# Page_C_ExCONNECTOR.net
KiCad netlist of a schematic drawn in Altium Designer
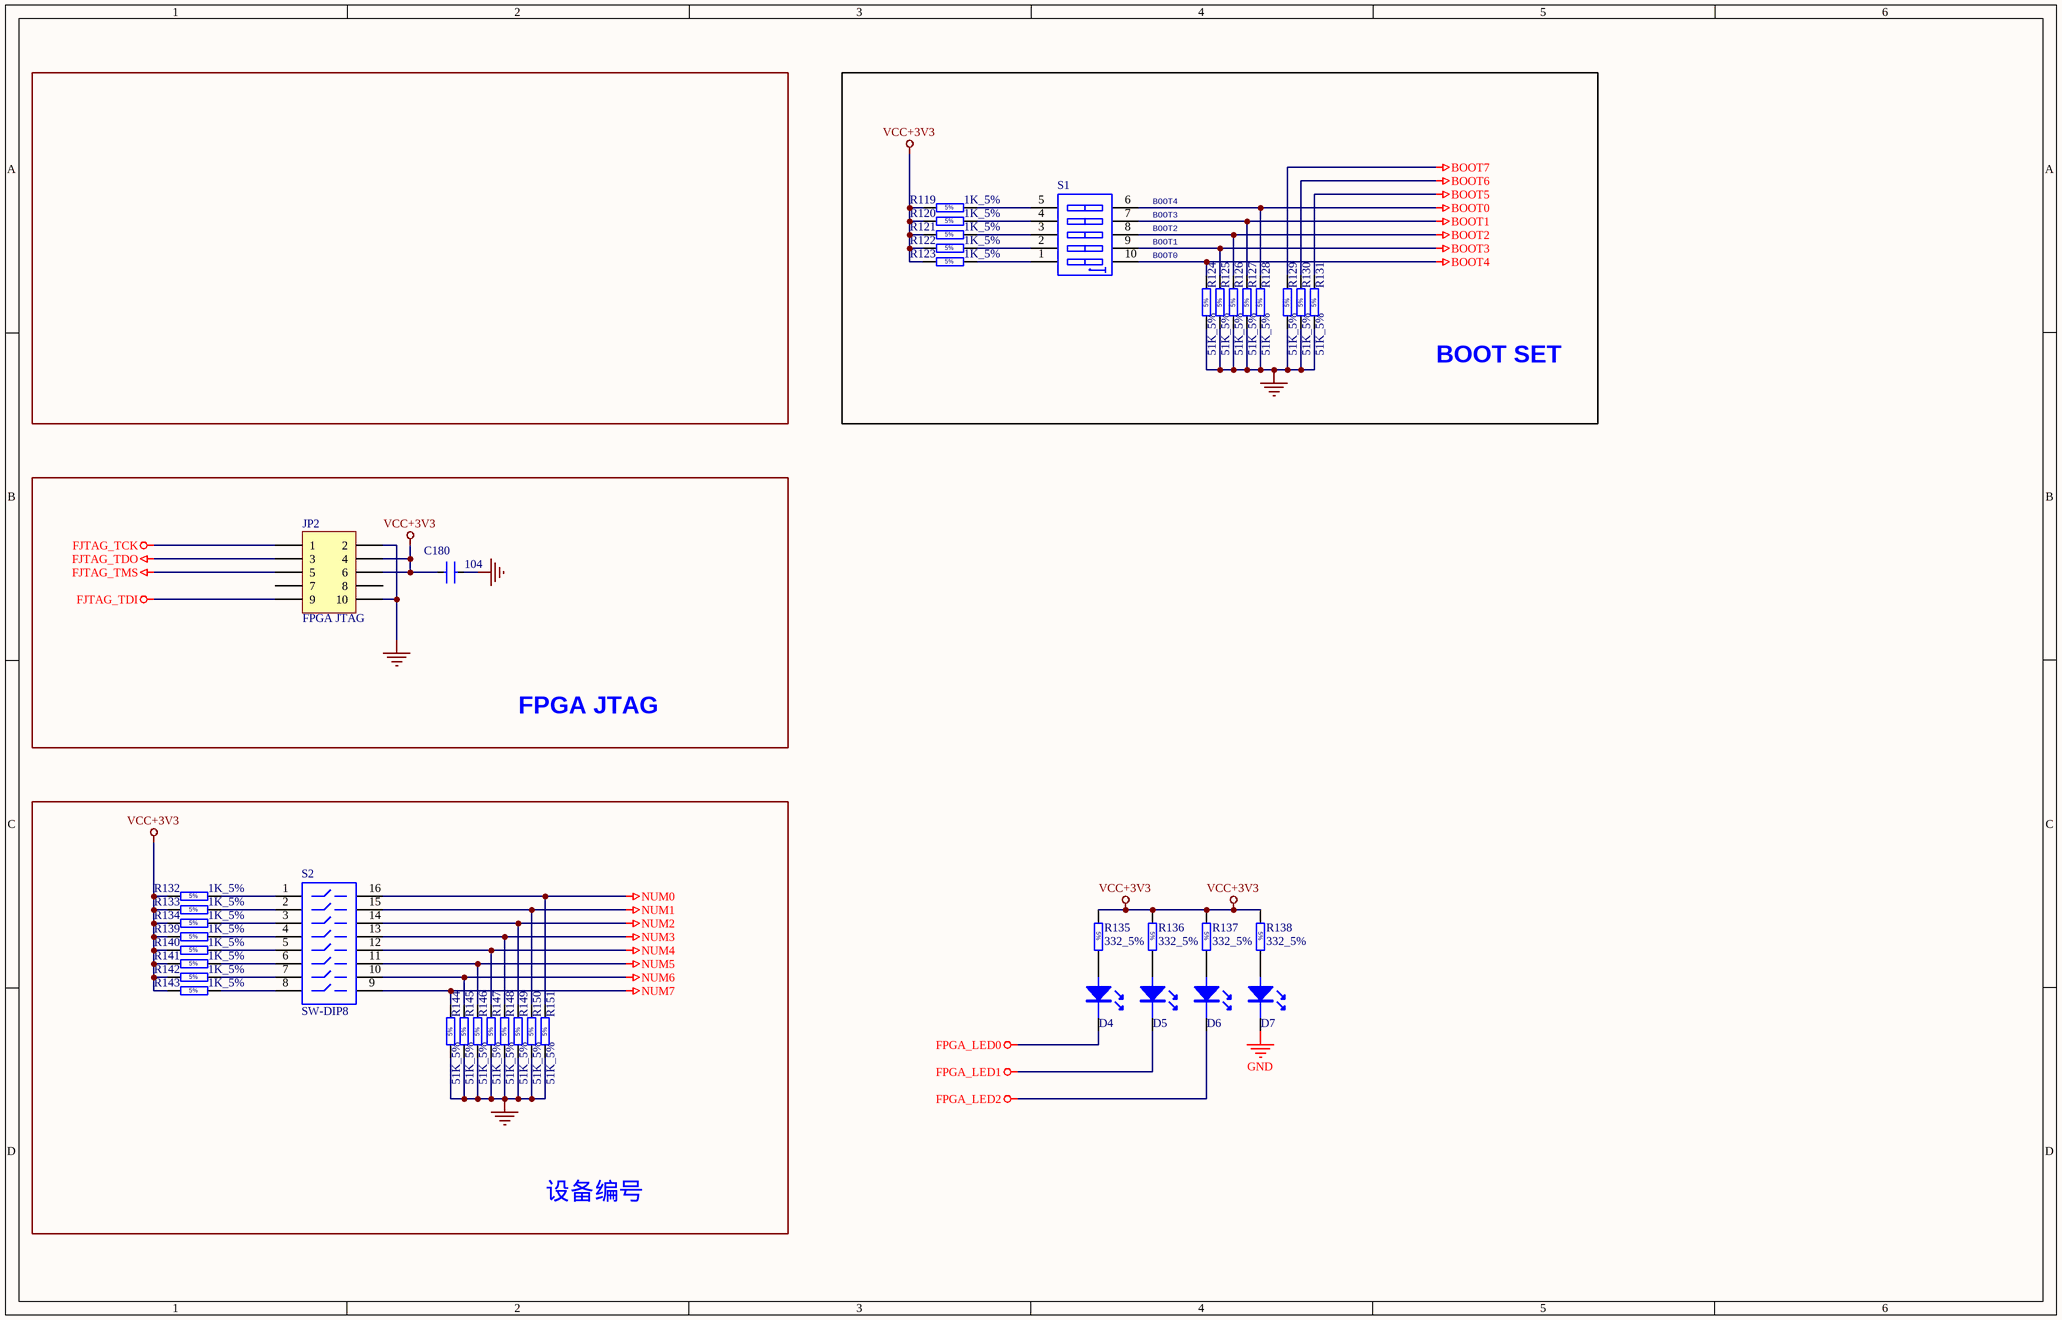
[diagram p0: Page C_ExCONNECTOR.SchDoc]

(export (version "E")
  (design (tool "Eeschema 10.0.6"))
  (components
    (comp (ref "C180")
      (value "104")
      (footprint "0603C")
      (description "C-X5R/X7R")
      (libsource (lib "贴片电阻电容") (part "C-X5R/X7R"))
    )
    (comp (ref "D4")
      (value "LED")
      (footprint "0805-LED")
      (libsource (lib "Miscellaneous Devices") (part "LED"))
    )
    (comp (ref "D5")
      (value "LED")
      (footprint "0805-LED")
      (libsource (lib "Miscellaneous Devices") (part "LED"))
    )
    (comp (ref "D6")
      (value "LED")
      (footprint "0805-LED")
      (libsource (lib "Miscellaneous Devices") (part "LED"))
    )
    (comp (ref "D7")
      (value "LED")
      (footprint "0805-LED")
      (libsource (lib "Miscellaneous Devices") (part "LED"))
    )
    (comp (ref "JP2")
      (value "FPGA JTAG")
      (footprint "HDR2X5")
      (description "Header, 5-Pin, Dual row")
      (fields (field (name "PUBLISHER") "Altium Limited"))
      (libsource (lib "Miscellaneous Connectors") (part "Header 5X2"))
    )
    (comp (ref "R119")
      (value "1K_5%")
      (footprint "0603R")
      (description "Resistor - 5%")
      (libsource (lib "贴片电阻电容") (part "Resistor - 5%"))
    )
    (comp (ref "R120")
      (value "1K_5%")
      (footprint "0603R")
      (description "Resistor - 5%")
      (libsource (lib "贴片电阻电容") (part "Resistor - 5%"))
    )
    (comp (ref "R121")
      (value "1K_5%")
      (footprint "0603R")
      (description "Resistor - 5%")
      (libsource (lib "贴片电阻电容") (part "Resistor - 5%"))
    )
    (comp (ref "R122")
      (value "1K_5%")
      (footprint "0603R")
      (description "Resistor - 5%")
      (libsource (lib "贴片电阻电容") (part "Resistor - 5%"))
    )
    (comp (ref "R123")
      (value "1K_5%")
      (footprint "0603R")
      (description "Resistor - 5%")
      (libsource (lib "贴片电阻电容") (part "Resistor - 5%"))
    )
    (comp (ref "R124")
      (value "51K_5%")
      (footprint "0603R")
      (description "Resistor - 5%")
      (libsource (lib "贴片电阻电容") (part "Resistor - 5%"))
    )
    (comp (ref "R125")
      (value "51K_5%")
      (footprint "0603R")
      (description "Resistor - 5%")
      (libsource (lib "贴片电阻电容") (part "Resistor - 5%"))
    )
    (comp (ref "R126")
      (value "51K_5%")
      (footprint "0603R")
      (description "Resistor - 5%")
      (libsource (lib "贴片电阻电容") (part "Resistor - 5%"))
    )
    (comp (ref "R127")
      (value "51K_5%")
      (footprint "0603R")
      (description "Resistor - 5%")
      (libsource (lib "贴片电阻电容") (part "Resistor - 5%"))
    )
    (comp (ref "R128")
      (value "51K_5%")
      (footprint "0603R")
      (description "Resistor - 5%")
      (libsource (lib "贴片电阻电容") (part "Resistor - 5%"))
    )
    (comp (ref "R129")
      (value "51K_5%")
      (footprint "0603R")
      (description "Resistor - 5%")
      (libsource (lib "贴片电阻电容") (part "Resistor - 5%"))
    )
    (comp (ref "R130")
      (value "51K_5%")
      (footprint "0603R")
      (description "Resistor - 5%")
      (libsource (lib "贴片电阻电容") (part "Resistor - 5%"))
    )
    (comp (ref "R131")
      (value "51K_5%")
      (footprint "0603R")
      (description "Resistor - 5%")
      (libsource (lib "贴片电阻电容") (part "Resistor - 5%"))
    )
    (comp (ref "R132")
      (value "1K_5%")
      (footprint "0603R")
      (description "Resistor - 5%")
      (libsource (lib "贴片电阻电容") (part "Resistor - 5%"))
    )
    (comp (ref "R133")
      (value "1K_5%")
      (footprint "0603R")
      (description "Resistor - 5%")
      (libsource (lib "贴片电阻电容") (part "Resistor - 5%"))
    )
    (comp (ref "R134")
      (value "1K_5%")
      (footprint "0603R")
      (description "Resistor - 5%")
      (libsource (lib "贴片电阻电容") (part "Resistor - 5%"))
    )
    (comp (ref "R135")
      (value "332_5%")
      (footprint "0603R")
      (description "Resistor - 5%")
      (libsource (lib "贴片电阻电容") (part "Resistor - 5%"))
    )
    (comp (ref "R136")
      (value "332_5%")
      (footprint "0603R")
      (description "Resistor - 5%")
      (libsource (lib "贴片电阻电容") (part "Resistor - 5%"))
    )
    (comp (ref "R137")
      (value "332_5%")
      (footprint "0603R")
      (description "Resistor - 5%")
      (libsource (lib "贴片电阻电容") (part "Resistor - 5%"))
    )
    (comp (ref "R138")
      (value "332_5%")
      (footprint "0603R")
      (description "Resistor - 5%")
      (libsource (lib "贴片电阻电容") (part "Resistor - 5%"))
    )
    (comp (ref "R139")
      (value "1K_5%")
      (footprint "0603R")
      (description "Resistor - 5%")
      (libsource (lib "贴片电阻电容") (part "Resistor - 5%"))
    )
    (comp (ref "R140")
      (value "1K_5%")
      (footprint "0603R")
      (description "Resistor - 5%")
      (libsource (lib "贴片电阻电容") (part "Resistor - 5%"))
    )
    (comp (ref "R141")
      (value "1K_5%")
      (footprint "0603R")
      (description "Resistor - 5%")
      (libsource (lib "贴片电阻电容") (part "Resistor - 5%"))
    )
    (comp (ref "R142")
      (value "1K_5%")
      (footprint "0603R")
      (description "Resistor - 5%")
      (libsource (lib "贴片电阻电容") (part "Resistor - 5%"))
    )
    (comp (ref "R143")
      (value "1K_5%")
      (footprint "0603R")
      (description "Resistor - 5%")
      (libsource (lib "贴片电阻电容") (part "Resistor - 5%"))
    )
    (comp (ref "R144")
      (value "51K_5%")
      (footprint "0603R")
      (description "Resistor - 5%")
      (libsource (lib "贴片电阻电容") (part "Resistor - 5%"))
    )
    (comp (ref "R145")
      (value "51K_5%")
      (footprint "0603R")
      (description "Resistor - 5%")
      (libsource (lib "贴片电阻电容") (part "Resistor - 5%"))
    )
    (comp (ref "R146")
      (value "51K_5%")
      (footprint "0603R")
      (description "Resistor - 5%")
      (libsource (lib "贴片电阻电容") (part "Resistor - 5%"))
    )
    (comp (ref "R147")
      (value "51K_5%")
      (footprint "0603R")
      (description "Resistor - 5%")
      (libsource (lib "贴片电阻电容") (part "Resistor - 5%"))
    )
    (comp (ref "R148")
      (value "51K_5%")
      (footprint "0603R")
      (description "Resistor - 5%")
      (libsource (lib "贴片电阻电容") (part "Resistor - 5%"))
    )
    (comp (ref "R149")
      (value "51K_5%")
      (footprint "0603R")
      (description "Resistor - 5%")
      (libsource (lib "贴片电阻电容") (part "Resistor - 5%"))
    )
    (comp (ref "R150")
      (value "51K_5%")
      (footprint "0603R")
      (description "Resistor - 5%")
      (libsource (lib "贴片电阻电容") (part "Resistor - 5%"))
    )
    (comp (ref "R151")
      (value "51K_5%")
      (footprint "0603R")
      (description "Resistor - 5%")
      (libsource (lib "贴片电阻电容") (part "Resistor - 5%"))
    )
    (comp (ref "S1")
      (value "SW DIP-5")
      (footprint "SW5-SO")
      (description "DIP Switch")
      (libsource (lib "Miscellaneous Devices") (part "SW DIP-5"))
    )
    (comp (ref "S2")
      (value "SW-DIP8")
      (footprint "SW8-SO")
      (libsource (lib "Miscellaneous Devices") (part "SW-DIP8"))
    )
  )
  (nets
    (net (code "1") (name "BOOT0") (class "Default")
      (node (ref "R128") (pin "2") (pinfunction "2_2") (pintype "passive"))
      (node (ref "S1") (pin "6") (pinfunction "B5_6") (pintype "passive"))
    )
    (net (code "2") (name "BOOT1") (class "Default")
      (node (ref "R127") (pin "2") (pinfunction "2_2") (pintype "passive"))
      (node (ref "S1") (pin "7") (pinfunction "B4_7") (pintype "passive"))
    )
    (net (code "3") (name "BOOT2") (class "Default")
      (node (ref "R126") (pin "2") (pinfunction "2_2") (pintype "passive"))
      (node (ref "S1") (pin "8") (pinfunction "B3_8") (pintype "passive"))
    )
    (net (code "4") (name "BOOT3") (class "Default")
      (node (ref "R125") (pin "2") (pinfunction "2_2") (pintype "passive"))
      (node (ref "S1") (pin "9") (pinfunction "B2_9") (pintype "passive"))
    )
    (net (code "5") (name "BOOT4") (class "Default")
      (node (ref "R124") (pin "2") (pinfunction "2_2") (pintype "passive"))
      (node (ref "S1") (pin "10") (pinfunction "B1_10") (pintype "passive"))
    )
    (net (code "6") (name "BOOT5") (class "Default")
      (node (ref "R131") (pin "2") (pinfunction "2_2") (pintype "passive"))
    )
    (net (code "7") (name "BOOT6") (class "Default")
      (node (ref "R130") (pin "2") (pinfunction "2_2") (pintype "passive"))
    )
    (net (code "8") (name "BOOT7") (class "Default")
      (node (ref "R129") (pin "2") (pinfunction "2_2") (pintype "passive"))
    )
    (net (code "9") (name "FJTAG_TCK") (class "Default")
      (node (ref "JP2") (pin "1") (pinfunction "1_1") (pintype "passive"))
    )
    (net (code "10") (name "FJTAG_TDI") (class "Default")
      (node (ref "JP2") (pin "9") (pinfunction "9_9") (pintype "passive"))
    )
    (net (code "11") (name "FJTAG_TDO") (class "Default")
      (node (ref "JP2") (pin "3") (pinfunction "3_3") (pintype "passive"))
    )
    (net (code "12") (name "FJTAG_TMS") (class "Default")
      (node (ref "JP2") (pin "5") (pinfunction "5_5") (pintype "passive"))
    )
    (net (code "13") (name "FPGA_LED0") (class "Default")
      (node (ref "D4") (pin "K") (pinfunction "K_K") (pintype "passive"))
    )
    (net (code "14") (name "FPGA_LED1") (class "Default")
      (node (ref "D5") (pin "K") (pinfunction "K_K") (pintype "passive"))
    )
    (net (code "15") (name "FPGA_LED2") (class "Default")
      (node (ref "D6") (pin "K") (pinfunction "K_K") (pintype "passive"))
    )
    (net (code "16") (name "GND") (class "Default")
      (node (ref "C180") (pin "2") (pinfunction "2_2") (pintype "passive"))
      (node (ref "D7") (pin "K") (pinfunction "K_K") (pintype "passive"))
      (node (ref "JP2") (pin "10") (pinfunction "10_10") (pintype "passive"))
      (node (ref "JP2") (pin "2") (pinfunction "2_2") (pintype "passive"))
      (node (ref "R124") (pin "1") (pinfunction "1_1") (pintype "passive"))
      (node (ref "R125") (pin "1") (pinfunction "1_1") (pintype "passive"))
      (node (ref "R126") (pin "1") (pinfunction "1_1") (pintype "passive"))
      (node (ref "R127") (pin "1") (pinfunction "1_1") (pintype "passive"))
      (node (ref "R128") (pin "1") (pinfunction "1_1") (pintype "passive"))
      (node (ref "R129") (pin "1") (pinfunction "1_1") (pintype "passive"))
      (node (ref "R130") (pin "1") (pinfunction "1_1") (pintype "passive"))
      (node (ref "R131") (pin "1") (pinfunction "1_1") (pintype "passive"))
      (node (ref "R144") (pin "1") (pinfunction "1_1") (pintype "passive"))
      (node (ref "R145") (pin "1") (pinfunction "1_1") (pintype "passive"))
      (node (ref "R146") (pin "1") (pinfunction "1_1") (pintype "passive"))
      (node (ref "R147") (pin "1") (pinfunction "1_1") (pintype "passive"))
      (node (ref "R148") (pin "1") (pinfunction "1_1") (pintype "passive"))
      (node (ref "R149") (pin "1") (pinfunction "1_1") (pintype "passive"))
      (node (ref "R150") (pin "1") (pinfunction "1_1") (pintype "passive"))
      (node (ref "R151") (pin "1") (pinfunction "1_1") (pintype "passive"))
    )
    (net (code "17") (name "NUM0") (class "Default")
      (node (ref "R151") (pin "2") (pinfunction "2_2") (pintype "passive"))
      (node (ref "S2") (pin "16") (pinfunction "16_16") (pintype "passive"))
    )
    (net (code "18") (name "NUM1") (class "Default")
      (node (ref "R150") (pin "2") (pinfunction "2_2") (pintype "passive"))
      (node (ref "S2") (pin "15") (pinfunction "15_15") (pintype "passive"))
    )
    (net (code "19") (name "NUM2") (class "Default")
      (node (ref "R149") (pin "2") (pinfunction "2_2") (pintype "passive"))
      (node (ref "S2") (pin "14") (pinfunction "14_14") (pintype "passive"))
    )
    (net (code "20") (name "NUM3") (class "Default")
      (node (ref "R148") (pin "2") (pinfunction "2_2") (pintype "passive"))
      (node (ref "S2") (pin "13") (pinfunction "13_13") (pintype "passive"))
    )
    (net (code "21") (name "NUM4") (class "Default")
      (node (ref "R147") (pin "2") (pinfunction "2_2") (pintype "passive"))
      (node (ref "S2") (pin "12") (pinfunction "12_12") (pintype "passive"))
    )
    (net (code "22") (name "NUM5") (class "Default")
      (node (ref "R146") (pin "2") (pinfunction "2_2") (pintype "passive"))
      (node (ref "S2") (pin "11") (pinfunction "11_11") (pintype "passive"))
    )
    (net (code "23") (name "NUM6") (class "Default")
      (node (ref "R145") (pin "2") (pinfunction "2_2") (pintype "passive"))
      (node (ref "S2") (pin "10") (pinfunction "10_10") (pintype "passive"))
    )
    (net (code "24") (name "NUM7") (class "Default")
      (node (ref "R144") (pin "2") (pinfunction "2_2") (pintype "passive"))
      (node (ref "S2") (pin "9") (pinfunction "9_9") (pintype "passive"))
    )
    (net (code "25") (name "Net-(D4-PadA)") (class "Default")
      (node (ref "D4") (pin "A") (pinfunction "A_A") (pintype "passive"))
      (node (ref "R135") (pin "2") (pinfunction "2_2") (pintype "passive"))
    )
    (net (code "26") (name "Net-(D5-PadA)") (class "Default")
      (node (ref "D5") (pin "A") (pinfunction "A_A") (pintype "passive"))
      (node (ref "R136") (pin "2") (pinfunction "2_2") (pintype "passive"))
    )
    (net (code "27") (name "Net-(D6-PadA)") (class "Default")
      (node (ref "D6") (pin "A") (pinfunction "A_A") (pintype "passive"))
      (node (ref "R137") (pin "2") (pinfunction "2_2") (pintype "passive"))
    )
    (net (code "28") (name "Net-(D7-PadA)") (class "Default")
      (node (ref "D7") (pin "A") (pinfunction "A_A") (pintype "passive"))
      (node (ref "R138") (pin "2") (pinfunction "2_2") (pintype "passive"))
    )
    (net (code "29") (name "Net-(R132-Pad2)") (class "Default")
      (node (ref "R132") (pin "2") (pinfunction "2_2") (pintype "passive"))
      (node (ref "S2") (pin "1") (pinfunction "1_1") (pintype "passive"))
    )
    (net (code "30") (name "Net-(R133-Pad2)") (class "Default")
      (node (ref "R133") (pin "2") (pinfunction "2_2") (pintype "passive"))
      (node (ref "S2") (pin "2") (pinfunction "2_2") (pintype "passive"))
    )
    (net (code "31") (name "Net-(R134-Pad2)") (class "Default")
      (node (ref "R134") (pin "2") (pinfunction "2_2") (pintype "passive"))
      (node (ref "S2") (pin "3") (pinfunction "3_3") (pintype "passive"))
    )
    (net (code "32") (name "Net-(R139-Pad2)") (class "Default")
      (node (ref "R139") (pin "2") (pinfunction "2_2") (pintype "passive"))
      (node (ref "S2") (pin "4") (pinfunction "4_4") (pintype "passive"))
    )
    (net (code "33") (name "Net-(R140-Pad2)") (class "Default")
      (node (ref "R140") (pin "2") (pinfunction "2_2") (pintype "passive"))
      (node (ref "S2") (pin "5") (pinfunction "5_5") (pintype "passive"))
    )
    (net (code "34") (name "Net-(R141-Pad2)") (class "Default")
      (node (ref "R141") (pin "2") (pinfunction "2_2") (pintype "passive"))
      (node (ref "S2") (pin "6") (pinfunction "6_6") (pintype "passive"))
    )
    (net (code "35") (name "Net-(R142-Pad2)") (class "Default")
      (node (ref "R142") (pin "2") (pinfunction "2_2") (pintype "passive"))
      (node (ref "S2") (pin "7") (pinfunction "7_7") (pintype "passive"))
    )
    (net (code "36") (name "Net-(R143-Pad2)") (class "Default")
      (node (ref "R143") (pin "2") (pinfunction "2_2") (pintype "passive"))
      (node (ref "S2") (pin "8") (pinfunction "8_8") (pintype "passive"))
    )
    (net (code "37") (name "Net-(S1-A1)") (class "Default")
      (node (ref "R123") (pin "2") (pinfunction "2_2") (pintype "passive"))
      (node (ref "S1") (pin "1") (pinfunction "A1_1") (pintype "passive"))
    )
    (net (code "38") (name "Net-(S1-A2)") (class "Default")
      (node (ref "R122") (pin "2") (pinfunction "2_2") (pintype "passive"))
      (node (ref "S1") (pin "2") (pinfunction "A2_2") (pintype "passive"))
    )
    (net (code "39") (name "Net-(S1-A3)") (class "Default")
      (node (ref "R121") (pin "2") (pinfunction "2_2") (pintype "passive"))
      (node (ref "S1") (pin "3") (pinfunction "A3_3") (pintype "passive"))
    )
    (net (code "40") (name "Net-(S1-A4)") (class "Default")
      (node (ref "R120") (pin "2") (pinfunction "2_2") (pintype "passive"))
      (node (ref "S1") (pin "4") (pinfunction "A4_4") (pintype "passive"))
    )
    (net (code "41") (name "Net-(S1-A5)") (class "Default")
      (node (ref "R119") (pin "2") (pinfunction "2_2") (pintype "passive"))
      (node (ref "S1") (pin "5") (pinfunction "A5_5") (pintype "passive"))
    )
    (net (code "42") (name "VCC+3V3") (class "Default")
      (node (ref "C180") (pin "1") (pinfunction "1_1") (pintype "passive"))
      (node (ref "JP2") (pin "4") (pinfunction "4_4") (pintype "passive"))
      (node (ref "JP2") (pin "6") (pinfunction "6_6") (pintype "passive"))
      (node (ref "R119") (pin "1") (pinfunction "1_1") (pintype "passive"))
      (node (ref "R120") (pin "1") (pinfunction "1_1") (pintype "passive"))
      (node (ref "R121") (pin "1") (pinfunction "1_1") (pintype "passive"))
      (node (ref "R122") (pin "1") (pinfunction "1_1") (pintype "passive"))
      (node (ref "R123") (pin "1") (pinfunction "1_1") (pintype "passive"))
      (node (ref "R132") (pin "1") (pinfunction "1_1") (pintype "passive"))
      (node (ref "R133") (pin "1") (pinfunction "1_1") (pintype "passive"))
      (node (ref "R134") (pin "1") (pinfunction "1_1") (pintype "passive"))
      (node (ref "R135") (pin "1") (pinfunction "1_1") (pintype "passive"))
      (node (ref "R136") (pin "1") (pinfunction "1_1") (pintype "passive"))
      (node (ref "R137") (pin "1") (pinfunction "1_1") (pintype "passive"))
      (node (ref "R138") (pin "1") (pinfunction "1_1") (pintype "passive"))
      (node (ref "R139") (pin "1") (pinfunction "1_1") (pintype "passive"))
      (node (ref "R140") (pin "1") (pinfunction "1_1") (pintype "passive"))
      (node (ref "R141") (pin "1") (pinfunction "1_1") (pintype "passive"))
      (node (ref "R142") (pin "1") (pinfunction "1_1") (pintype "passive"))
      (node (ref "R143") (pin "1") (pinfunction "1_1") (pintype "passive"))
    )
    (net (code "43") (name "unconnected-(JP2-Pad7)") (class "Default")
      (node (ref "JP2") (pin "7") (pinfunction "7_7") (pintype "passive"))
    )
    (net (code "44") (name "unconnected-(JP2-Pad8)") (class "Default")
      (node (ref "JP2") (pin "8") (pinfunction "8_8") (pintype "passive"))
    )
  )
)
